# IMU-SENSOR.net
KiCad netlist of a schematic drawn in Altium Designer
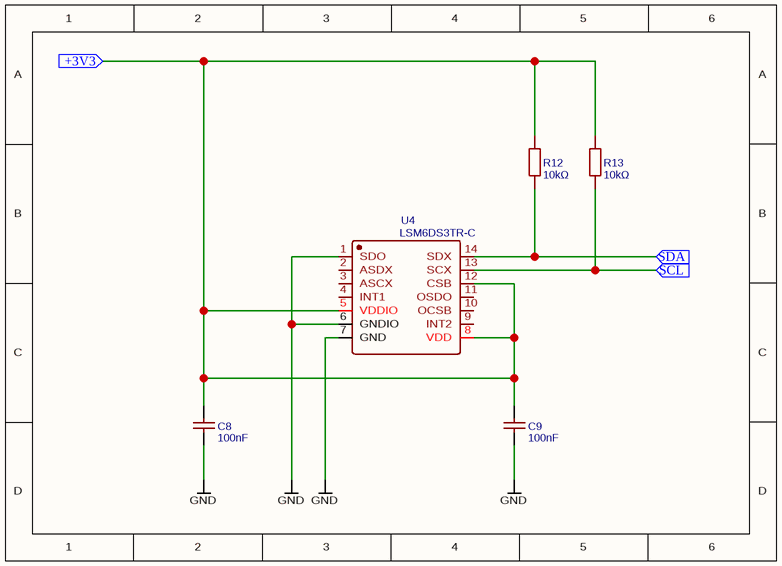
[diagram p0: IMU-SENSOR.schdoc]

(export (version "E")
  (design (tool "Eeschema 10.0.6"))
  (components
    (comp (ref "C8")
      (value "100nF")
      (fields
        (field (name "BOM_MANUFACTURER PART") "CL10B104KO8NNNC")
        (field (name "BOM_SUPPLIER PART") "C66501")
      )
      (libsource (lib "altium-import") (part "root_1_100nF_"))
    )
    (comp (ref "C9")
      (value "100nF")
      (fields
        (field (name "BOM_MANUFACTURER PART") "CL10B104KO8NNNC")
        (field (name "BOM_SUPPLIER PART") "C66501")
      )
      (libsource (lib "altium-import") (part "root_1_100nF_"))
    )
    (comp (ref "R12")
      (value "10kΩ")
      (fields
        (field (name "BOM_SUPPLIER PART") "C115324")
        (field (name "BOM_MANUFACTURER PART") "RS-03K1002FT")
        (field (name "CONTRIBUTOR") "LCSC")
      )
      (libsource (lib "altium-import") (part "root_1_10kΩ_"))
    )
    (comp (ref "R13")
      (value "10kΩ")
      (fields
        (field (name "BOM_SUPPLIER PART") "C115324")
        (field (name "BOM_MANUFACTURER PART") "RS-03K1002FT")
        (field (name "CONTRIBUTOR") "LCSC")
      )
      (libsource (lib "altium-import") (part "root_1_10kΩ_"))
    )
    (comp (ref "U4")
      (value "LSM6DS3TR-C")
      (fields (field (name "BOM_SUPPLIER PART") "C967633"))
      (libsource (lib "altium-import") (part "root_0_LSM6DS3TR-C_"))
    )
  )
  (nets
    (net (code "1") (name "/+3V3") (class "Default")
      (node (ref "C8") (pin "2") (pinfunction "2_2") (pintype "passive"))
      (node (ref "C9") (pin "2") (pinfunction "2_2") (pintype "passive"))
      (node (ref "R12") (pin "2") (pinfunction "2_2") (pintype "passive"))
      (node (ref "R13") (pin "2") (pinfunction "2_2") (pintype "passive"))
      (node (ref "U4") (pin "12") (pinfunction "CSB_12") (pintype "passive"))
      (node (ref "U4") (pin "5") (pinfunction "VDDIO_5") (pintype "passive"))
      (node (ref "U4") (pin "8") (pinfunction "VDD_8") (pintype "passive"))
    )
    (net (code "2") (name "/SCL") (class "Default")
      (node (ref "R13") (pin "1") (pinfunction "1_1") (pintype "passive"))
      (node (ref "U4") (pin "13") (pinfunction "SCX_13") (pintype "passive"))
    )
    (net (code "3") (name "/SDA") (class "Default")
      (node (ref "R12") (pin "1") (pinfunction "1_1") (pintype "passive"))
      (node (ref "U4") (pin "14") (pinfunction "SDX_14") (pintype "passive"))
    )
    (net (code "4") (name "GND") (class "Default")
      (node (ref "C8") (pin "1") (pinfunction "1_1") (pintype "passive"))
      (node (ref "C9") (pin "1") (pinfunction "1_1") (pintype "passive"))
      (node (ref "U4") (pin "1") (pinfunction "SDO_1") (pintype "passive"))
      (node (ref "U4") (pin "6") (pinfunction "GNDIO_6") (pintype "passive"))
      (node (ref "U4") (pin "7") (pinfunction "GND_7") (pintype "passive"))
    )
    (net (code "5") (name "unconnected-(U4-ASCX-Pad3)") (class "Default")
      (node (ref "U4") (pin "3") (pinfunction "ASCX_3") (pintype "passive"))
    )
    (net (code "6") (name "unconnected-(U4-ASDX-Pad2)") (class "Default")
      (node (ref "U4") (pin "2") (pinfunction "ASDX_2") (pintype "passive"))
    )
    (net (code "7") (name "unconnected-(U4-INT1-Pad4)") (class "Default")
      (node (ref "U4") (pin "4") (pinfunction "INT1_4") (pintype "passive"))
    )
    (net (code "8") (name "unconnected-(U4-INT2-Pad9)") (class "Default")
      (node (ref "U4") (pin "9") (pinfunction "INT2_9") (pintype "passive"))
    )
    (net (code "9") (name "unconnected-(U4-OCSB-Pad10)") (class "Default")
      (node (ref "U4") (pin "10") (pinfunction "OCSB_10") (pintype "passive"))
    )
    (net (code "10") (name "unconnected-(U4-OSDO-Pad11)") (class "Default")
      (node (ref "U4") (pin "11") (pinfunction "OSDO_11") (pintype "passive"))
    )
  )
)
